# bottom_simp_motor.net
KiCad netlist of a schematic drawn in Altium Designer
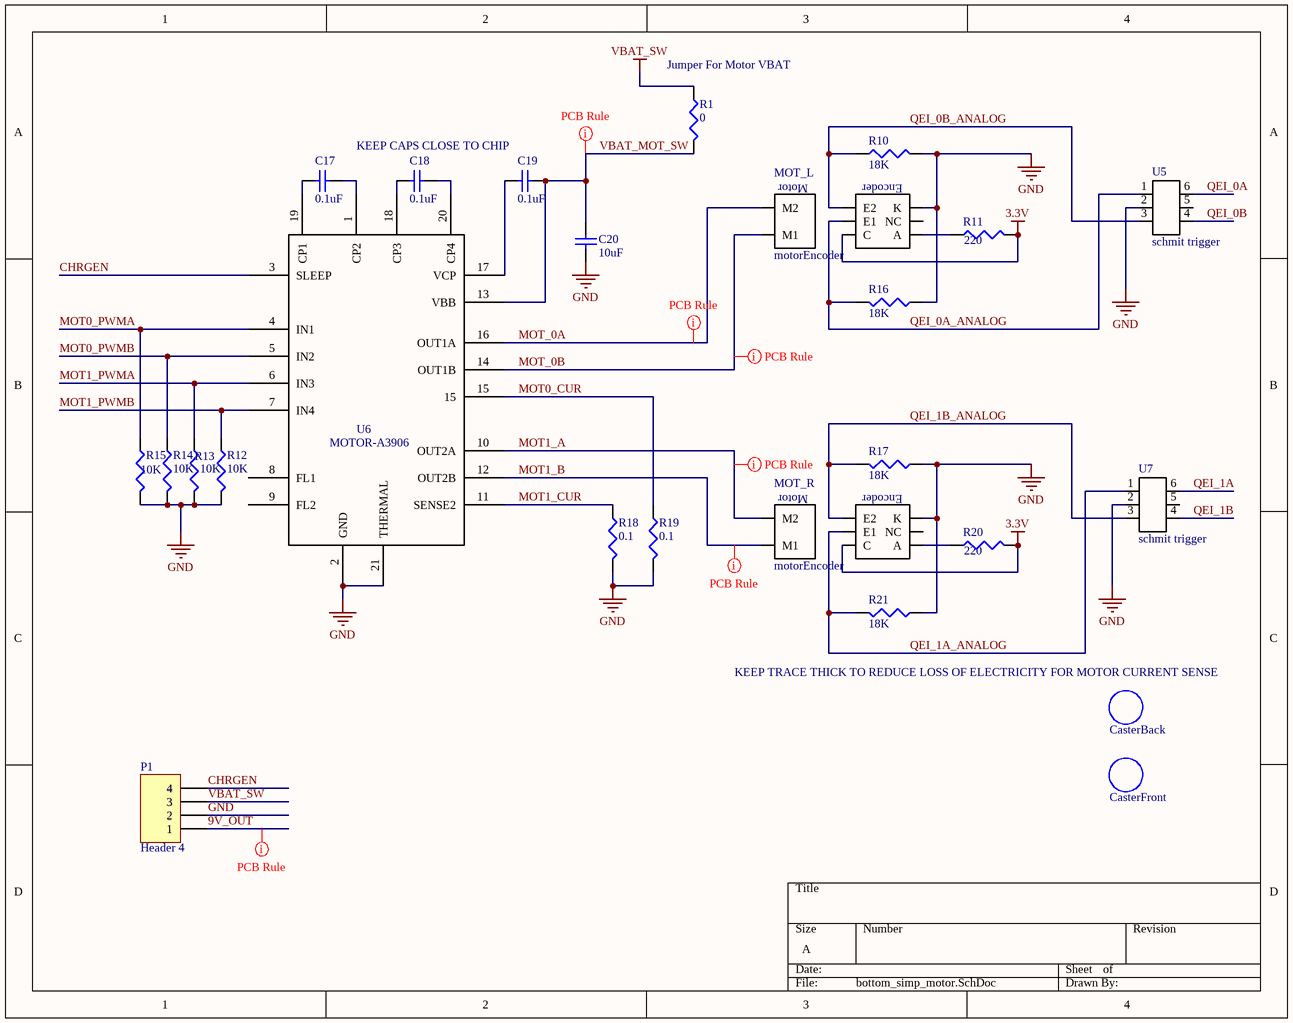
[diagram p0: bottom_simp_motor.SchDoc]

(export (version "E")
  (design (tool "Eeschema 10.0.6"))
  (components
    (comp (ref "C17")
      (value "0.1uF")
      (footprint "CAPC1005L")
      (description "Capacitor (Semiconductor SIM Model)")
      (fields (field (name "Comment") "Cap Semi") (field (name "PUBLISHER") "Altium Limited"))
      (libsource (lib "Miscellaneous Devices") (part "Cap Semi"))
    )
    (comp (ref "C18")
      (value "0.1uF")
      (footprint "CAPC1005L")
      (description "Capacitor (Semiconductor SIM Model)")
      (fields (field (name "Comment") "Cap Semi") (field (name "PUBLISHER") "Altium Limited"))
      (libsource (lib "Miscellaneous Devices") (part "Cap Semi"))
    )
    (comp (ref "C19")
      (value "0.1uF")
      (footprint "CAPC1005L")
      (description "Capacitor (Semiconductor SIM Model)")
      (fields (field (name "Comment") "Cap Semi") (field (name "PUBLISHER") "Altium Limited"))
      (libsource (lib "Miscellaneous Devices") (part "Cap Semi"))
    )
    (comp (ref "C20")
      (value "10uF")
      (footprint "CAPC1608L")
      (description "Capacitor (Semiconductor SIM Model)")
      (fields (field (name "Comment") "Cap Semi") (field (name "PUBLISHER") "Altium Limited"))
      (libsource (lib "Miscellaneous Devices") (part "Cap Semi"))
    )
    (comp (ref "CasterBack")
      (value "non connect")
      (footprint "3/8\"Caster")
      (description "This is just a space saver to get the caster onto the pcb")
      (libsource (lib "mrone") (part "Caster"))
    )
    (comp (ref "CasterFront")
      (value "non connect")
      (footprint "3/8\"Caster")
      (description "This is just a space saver to get the caster onto the pcb")
      (libsource (lib "mrone") (part "Caster"))
    )
    (comp (ref "MOT_L")
      (value "motorEncoder")
      (footprint "motorEncoder")
      (libsource (lib "mrone") (part "motorEncoder"))
    )
    (comp (ref "MOT_R")
      (value "motorEncoder")
      (footprint "motorEncoder")
      (libsource (lib "mrone") (part "motorEncoder"))
    )
    (comp (ref "P1")
      (value "Header 4")
      (footprint "HDR1X4")
      (description "Header, 4-Pin")
      (fields (field (name "PUBLISHER") "Altium Limited"))
      (libsource (lib "Miscellaneous Connectors") (part "Header 4"))
    )
    (comp (ref "R1")
      (value "0")
      (footprint "RESC3225L")
      (description "Resistor")
      (fields (field (name "Comment") "Res3") (field (name "PUBLISHER") "Altium Limited"))
      (libsource (lib "Miscellaneous Devices") (part "Res3"))
    )
    (comp (ref "R10")
      (value "18K")
      (footprint "RESC1608L")
      (description "Resistor")
      (fields (field (name "PUBLISHER") "Altium Limited"))
      (libsource (lib "Miscellaneous Devices") (part "Res3"))
    )
    (comp (ref "R11")
      (value "220")
      (footprint "RESC1608L")
      (description "Resistor")
      (fields (field (name "PUBLISHER") "Altium Limited"))
      (libsource (lib "Miscellaneous Devices") (part "Res3"))
    )
    (comp (ref "R12")
      (value "10K")
      (footprint "RESC1608L")
      (description "Resistor")
      (fields (field (name "Comment") "Res3") (field (name "PUBLISHER") "Altium Limited"))
      (libsource (lib "Miscellaneous Devices") (part "Res3"))
    )
    (comp (ref "R13")
      (value "10K")
      (footprint "RESC1608L")
      (description "Resistor")
      (fields (field (name "Comment") "Res3") (field (name "PUBLISHER") "Altium Limited"))
      (libsource (lib "Miscellaneous Devices") (part "Res3"))
    )
    (comp (ref "R14")
      (value "10K")
      (footprint "RESC1608L")
      (description "Resistor")
      (fields (field (name "Comment") "Res3") (field (name "PUBLISHER") "Altium Limited"))
      (libsource (lib "Miscellaneous Devices") (part "Res3"))
    )
    (comp (ref "R15")
      (value "10K")
      (footprint "RESC1608L")
      (description "Resistor")
      (fields (field (name "Comment") "Res3") (field (name "PUBLISHER") "Altium Limited"))
      (libsource (lib "Miscellaneous Devices") (part "Res3"))
    )
    (comp (ref "R16")
      (value "18K")
      (footprint "RESC1608L")
      (description "Resistor")
      (fields (field (name "PUBLISHER") "Altium Limited"))
      (libsource (lib "Miscellaneous Devices") (part "Res3"))
    )
    (comp (ref "R17")
      (value "18K")
      (footprint "RESC1608L")
      (description "Resistor")
      (fields (field (name "PUBLISHER") "Altium Limited"))
      (libsource (lib "Miscellaneous Devices") (part "Res3"))
    )
    (comp (ref "R18")
      (value "0.1")
      (footprint "RESC1608L")
      (description "Resistor")
      (fields (field (name "Comment") "Res3") (field (name "PUBLISHER") "Altium Limited"))
      (libsource (lib "Miscellaneous Devices") (part "Res3"))
    )
    (comp (ref "R19")
      (value "0.1")
      (footprint "RESC1608L")
      (description "Resistor")
      (fields (field (name "Comment") "Res3") (field (name "PUBLISHER") "Altium Limited"))
      (libsource (lib "Miscellaneous Devices") (part "Res3"))
    )
    (comp (ref "R20")
      (value "220")
      (footprint "RESC1608L")
      (description "Resistor")
      (fields (field (name "PUBLISHER") "Altium Limited"))
      (libsource (lib "Miscellaneous Devices") (part "Res3"))
    )
    (comp (ref "R21")
      (value "18K")
      (footprint "RESC1608L")
      (description "Resistor")
      (fields (field (name "PUBLISHER") "Altium Limited"))
      (libsource (lib "Miscellaneous Devices") (part "Res3"))
    )
    (comp (ref "U5")
      (value "schmit trigger")
      (footprint "DCK(R-PDSO-C6)")
      (libsource (lib "mrone") (part "schmit trigger"))
    )
    (comp (ref "U6")
      (value "MOTOR-A3906")
      (footprint "QFN-20")
      (libsource (lib "V2_altium") (part "MOTOR-A3906"))
    )
    (comp (ref "U7")
      (value "schmit trigger")
      (footprint "DCK(R-PDSO-C6)")
      (libsource (lib "mrone") (part "schmit trigger"))
    )
  )
  (nets
    (net (code "1") (name "/9V_OUT") (class "Default")
      (node (ref "P1") (pin "1") (pinfunction "1_1") (pintype "passive"))
    )
    (net (code "3") (name "/CHRGEN") (class "Default")
      (node (ref "P1") (pin "4") (pinfunction "4_4") (pintype "passive"))
      (node (ref "U6") (pin "3") (pinfunction "SLEEP_3") (pintype "passive"))
    )
    (net (code "4") (name "/MOT0_CUR") (class "Default")
      (node (ref "R19") (pin "1") (pinfunction "1_1") (pintype "passive"))
      (node (ref "U6") (pin "15") (pinfunction "15_15") (pintype "passive"))
    )
    (net (code "5") (name "/MOT0_PWMA") (class "Default")
      (node (ref "R15") (pin "1") (pinfunction "1_1") (pintype "passive"))
      (node (ref "U6") (pin "4") (pinfunction "IN1_4") (pintype "passive"))
    )
    (net (code "6") (name "/MOT0_PWMB") (class "Default")
      (node (ref "R14") (pin "1") (pinfunction "1_1") (pintype "passive"))
      (node (ref "U6") (pin "5") (pinfunction "IN2_5") (pintype "passive"))
    )
    (net (code "7") (name "/MOT1_A") (class "Default")
      (node (ref "MOT_R") (pin "M2") (pinfunction "M2_M2") (pintype "passive"))
      (node (ref "U6") (pin "10") (pinfunction "OUT2A_10") (pintype "passive"))
    )
    (net (code "8") (name "/MOT1_B") (class "Default")
      (node (ref "MOT_R") (pin "M1") (pinfunction "M1_M1") (pintype "passive"))
      (node (ref "U6") (pin "12") (pinfunction "OUT2B_12") (pintype "passive"))
    )
    (net (code "9") (name "/MOT1_CUR") (class "Default")
      (node (ref "R18") (pin "1") (pinfunction "1_1") (pintype "passive"))
      (node (ref "U6") (pin "11") (pinfunction "SENSE2_11") (pintype "passive"))
    )
    (net (code "10") (name "/MOT1_PWMA") (class "Default")
      (node (ref "R13") (pin "1") (pinfunction "1_1") (pintype "passive"))
      (node (ref "U6") (pin "6") (pinfunction "IN3_6") (pintype "passive"))
    )
    (net (code "11") (name "/MOT1_PWMB") (class "Default")
      (node (ref "R12") (pin "1") (pinfunction "1_1") (pintype "passive"))
      (node (ref "U6") (pin "7") (pinfunction "IN4_7") (pintype "passive"))
    )
    (net (code "12") (name "/MOT_0A") (class "Default")
      (node (ref "MOT_L") (pin "M2") (pinfunction "M2_M2") (pintype "passive"))
      (node (ref "U6") (pin "16") (pinfunction "OUT1A_16") (pintype "passive"))
    )
    (net (code "13") (name "/MOT_0B") (class "Default")
      (node (ref "MOT_L") (pin "M1") (pinfunction "M1_M1") (pintype "passive"))
      (node (ref "U6") (pin "14") (pinfunction "OUT1B_14") (pintype "passive"))
    )
    (net (code "14") (name "/QEI_0A") (class "Default")
      (node (ref "U5") (pin "6") (pinfunction "4_6") (pintype "passive"))
    )
    (net (code "15") (name "/QEI_0A_ANALOG") (class "Default")
      (node (ref "MOT_L") (pin "E1") (pinfunction "E1_E1") (pintype "passive"))
      (node (ref "R16") (pin "2") (pinfunction "2_2") (pintype "passive"))
      (node (ref "U5") (pin "1") (pinfunction "1_1") (pintype "passive"))
    )
    (net (code "16") (name "/QEI_0B") (class "Default")
      (node (ref "U5") (pin "4") (pinfunction "4_4") (pintype "passive"))
    )
    (net (code "17") (name "/QEI_0B_ANALOG") (class "Default")
      (node (ref "MOT_L") (pin "E2") (pinfunction "E2_E2") (pintype "passive"))
      (node (ref "R10") (pin "1") (pinfunction "1_1") (pintype "passive"))
      (node (ref "U5") (pin "3") (pinfunction "3_3") (pintype "passive"))
    )
    (net (code "18") (name "/QEI_1A") (class "Default")
      (node (ref "U7") (pin "6") (pinfunction "4_6") (pintype "passive"))
    )
    (net (code "19") (name "/QEI_1A_ANALOG") (class "Default")
      (node (ref "MOT_R") (pin "E1") (pinfunction "E1_E1") (pintype "passive"))
      (node (ref "R21") (pin "2") (pinfunction "2_2") (pintype "passive"))
      (node (ref "U7") (pin "1") (pinfunction "1_1") (pintype "passive"))
    )
    (net (code "20") (name "/QEI_1B") (class "Default")
      (node (ref "U7") (pin "4") (pinfunction "4_4") (pintype "passive"))
    )
    (net (code "21") (name "/QEI_1B_ANALOG") (class "Default")
      (node (ref "MOT_R") (pin "E2") (pinfunction "E2_E2") (pintype "passive"))
      (node (ref "R17") (pin "2") (pinfunction "2_2") (pintype "passive"))
      (node (ref "U7") (pin "3") (pinfunction "3_3") (pintype "passive"))
    )
    (net (code "22") (name "/VBAT_MOT_SW") (class "Default")
      (node (ref "C19") (pin "1") (pinfunction "1_1") (pintype "passive"))
      (node (ref "C20") (pin "2") (pinfunction "2_2") (pintype "passive"))
      (node (ref "R1") (pin "2") (pinfunction "2_2") (pintype "passive"))
      (node (ref "U6") (pin "13") (pinfunction "VBB_13") (pintype "passive"))
    )
    (net (code "23") (name "3.3V") (class "Default")
      (node (ref "MOT_L") (pin "C") (pinfunction "C_C") (pintype "passive"))
      (node (ref "MOT_R") (pin "C") (pinfunction "C_C") (pintype "passive"))
      (node (ref "R11") (pin "2") (pinfunction "2_2") (pintype "passive"))
      (node (ref "R20") (pin "2") (pinfunction "2_2") (pintype "passive"))
    )
    (net (code "24") (name "GND") (class "Default")
      (node (ref "C20") (pin "1") (pinfunction "1_1") (pintype "passive"))
      (node (ref "MOT_L") (pin "K") (pinfunction "K_K") (pintype "passive"))
      (node (ref "MOT_R") (pin "K") (pinfunction "K_K") (pintype "passive"))
      (node (ref "P1") (pin "2") (pinfunction "2_2") (pintype "passive"))
      (node (ref "R10") (pin "2") (pinfunction "2_2") (pintype "passive"))
      (node (ref "R12") (pin "2") (pinfunction "2_2") (pintype "passive"))
      (node (ref "R13") (pin "2") (pinfunction "2_2") (pintype "passive"))
      (node (ref "R14") (pin "2") (pinfunction "2_2") (pintype "passive"))
      (node (ref "R15") (pin "2") (pinfunction "2_2") (pintype "passive"))
      (node (ref "R16") (pin "1") (pinfunction "1_1") (pintype "passive"))
      (node (ref "R17") (pin "1") (pinfunction "1_1") (pintype "passive"))
      (node (ref "R18") (pin "2") (pinfunction "2_2") (pintype "passive"))
      (node (ref "R19") (pin "2") (pinfunction "2_2") (pintype "passive"))
      (node (ref "R21") (pin "1") (pinfunction "1_1") (pintype "passive"))
      (node (ref "U5") (pin "2") (pinfunction "2_2") (pintype "passive"))
      (node (ref "U6") (pin "2") (pinfunction "GND_2") (pintype "passive"))
      (node (ref "U6") (pin "21") (pinfunction "THERMAL_21") (pintype "passive"))
      (node (ref "U7") (pin "2") (pinfunction "2_2") (pintype "passive"))
    )
    (net (code "25") (name "Net-(MOT_L-PadA)") (class "Default")
      (node (ref "MOT_L") (pin "A") (pinfunction "A_A") (pintype "passive"))
      (node (ref "R11") (pin "1") (pinfunction "1_1") (pintype "passive"))
    )
    (net (code "26") (name "Net-(MOT_R-PadA)") (class "Default")
      (node (ref "MOT_R") (pin "A") (pinfunction "A_A") (pintype "passive"))
      (node (ref "R20") (pin "1") (pinfunction "1_1") (pintype "passive"))
    )
    (net (code "27") (name "Net-(U6-CP1)") (class "Default")
      (node (ref "C17") (pin "1") (pinfunction "1_1") (pintype "passive"))
      (node (ref "U6") (pin "19") (pinfunction "CP1_19") (pintype "passive"))
    )
    (net (code "28") (name "Net-(U6-CP2)") (class "Default")
      (node (ref "C17") (pin "2") (pinfunction "2_2") (pintype "passive"))
      (node (ref "U6") (pin "1") (pinfunction "CP2_1") (pintype "passive"))
    )
    (net (code "29") (name "Net-(U6-CP3)") (class "Default")
      (node (ref "C18") (pin "1") (pinfunction "1_1") (pintype "passive"))
      (node (ref "U6") (pin "18") (pinfunction "CP3_18") (pintype "passive"))
    )
    (net (code "30") (name "Net-(U6-CP4)") (class "Default")
      (node (ref "C18") (pin "2") (pinfunction "2_2") (pintype "passive"))
      (node (ref "U6") (pin "20") (pinfunction "CP4_20") (pintype "passive"))
    )
    (net (code "31") (name "Net-(U6-VCP)") (class "Default")
      (node (ref "C19") (pin "2") (pinfunction "2_2") (pintype "passive"))
      (node (ref "U6") (pin "17") (pinfunction "VCP_17") (pintype "passive"))
    )
    (net (code "32") (name "VBAT_SW") (class "Default")
      (node (ref "P1") (pin "3") (pinfunction "3_3") (pintype "passive"))
      (node (ref "R1") (pin "1") (pinfunction "1_1") (pintype "passive"))
    )
    (net (code "33") (name "unconnected-(MOT_L-PadNC)") (class "Default")
      (node (ref "MOT_L") (pin "NC") (pinfunction "NC_NC") (pintype "passive"))
    )
    (net (code "34") (name "unconnected-(MOT_R-PadNC)") (class "Default")
      (node (ref "MOT_R") (pin "NC") (pinfunction "NC_NC") (pintype "passive"))
    )
    (net (code "35") (name "unconnected-(U5-Pad5)") (class "Default")
      (node (ref "U5") (pin "5") (pinfunction "5_5") (pintype "passive"))
    )
    (net (code "36") (name "unconnected-(U6-FL1-Pad8)") (class "Default")
      (node (ref "U6") (pin "8") (pinfunction "FL1_8") (pintype "passive"))
    )
    (net (code "37") (name "unconnected-(U6-FL2-Pad9)") (class "Default")
      (node (ref "U6") (pin "9") (pinfunction "FL2_9") (pintype "passive"))
    )
    (net (code "38") (name "unconnected-(U7-Pad5)") (class "Default")
      (node (ref "U7") (pin "5") (pinfunction "5_5") (pintype "passive"))
    )
  )
)
